# DroneCode_probe-v22.net
KiCad netlist of a schematic drawn in EAGLE
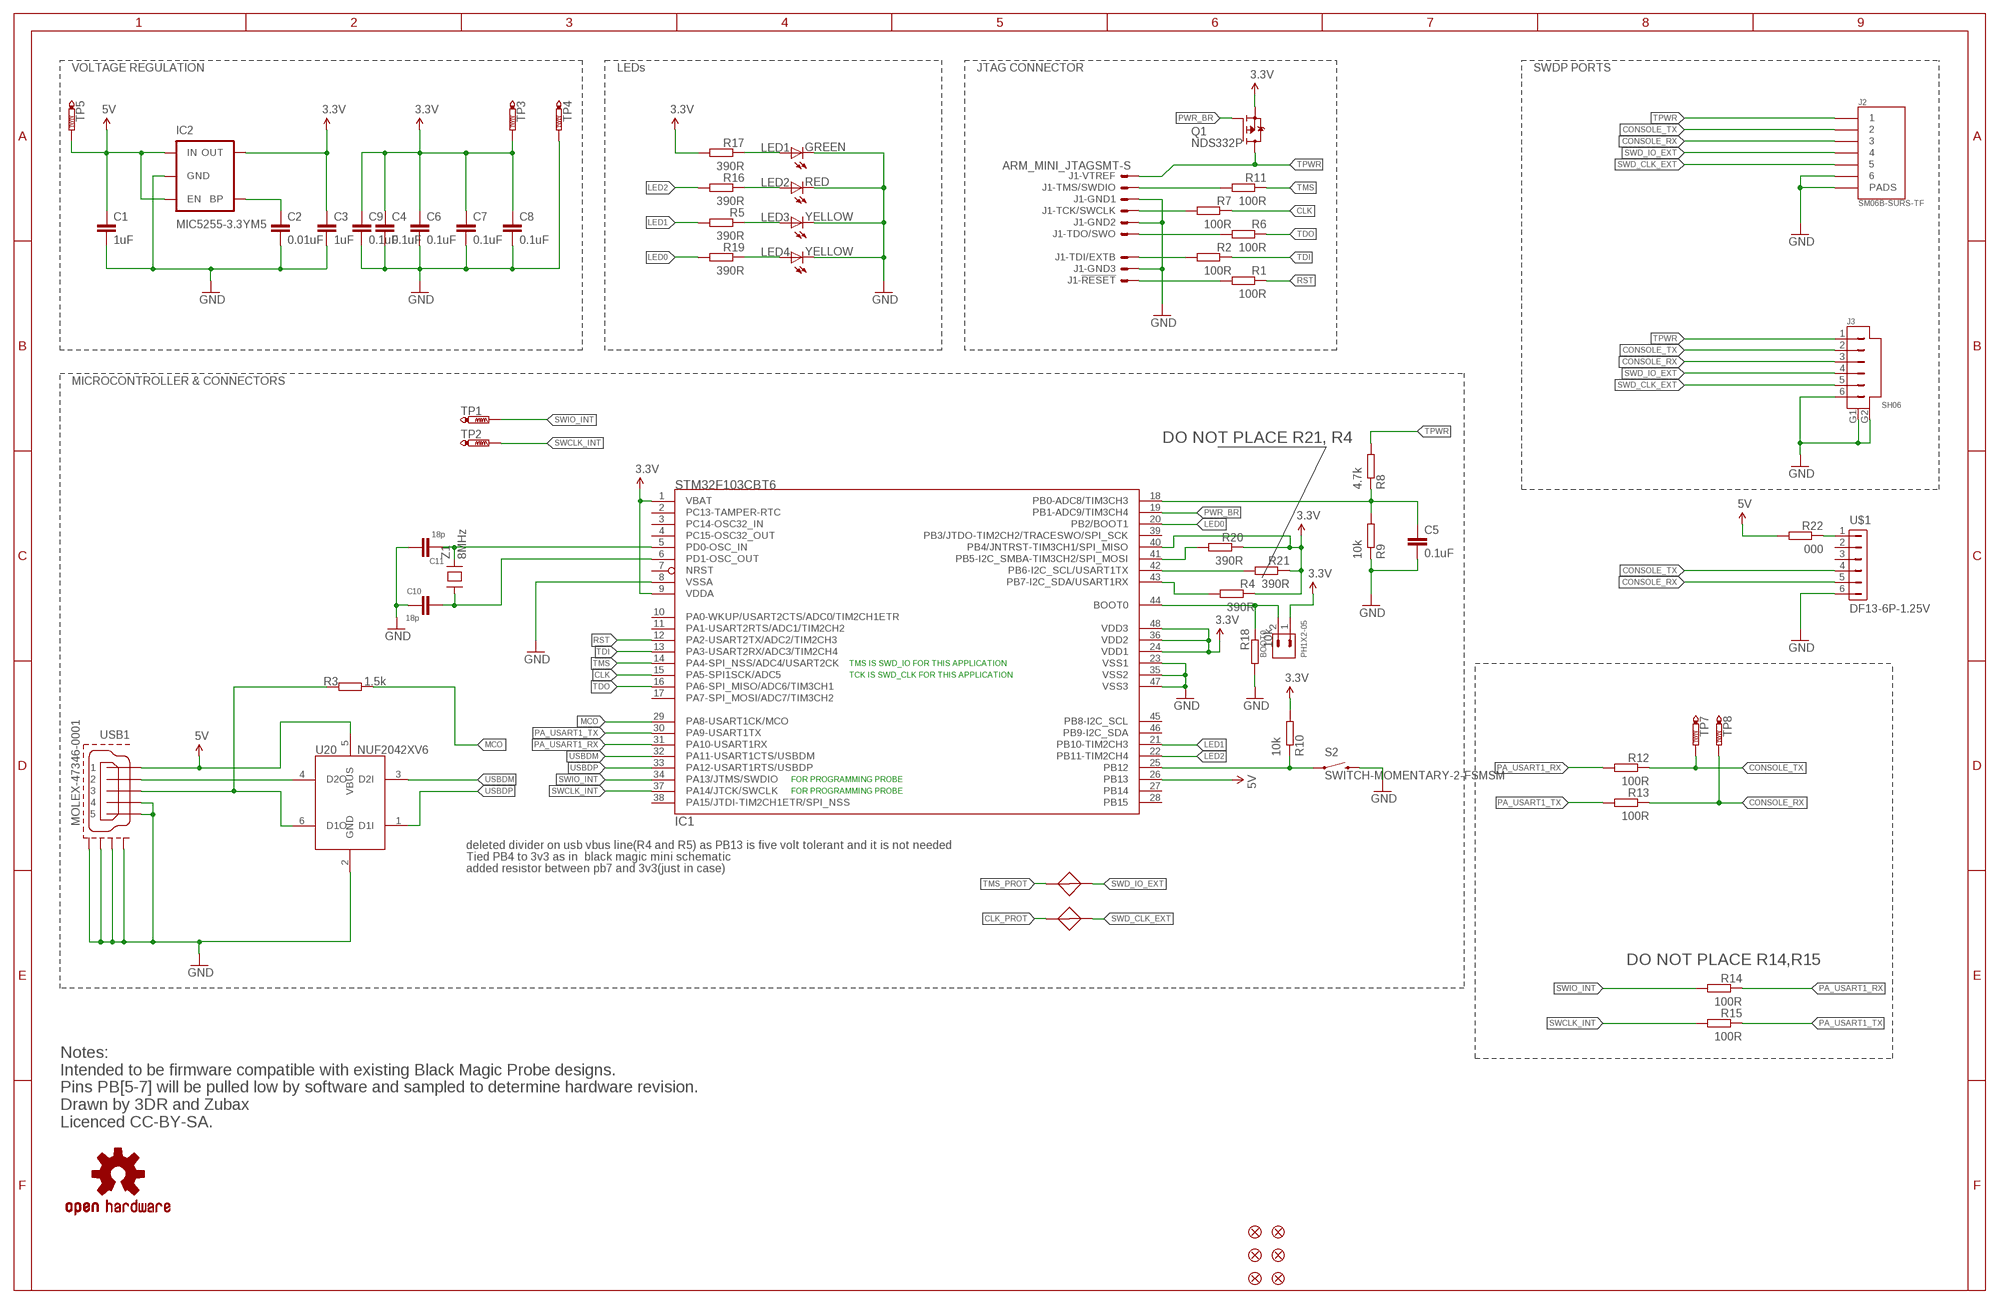
[diagram p0: schematic, sheet 1]

(export (version "E")
  (design (tool "Eeschema 10.0.6"))
  (components
    (comp (ref "BOOT0")
      (value "PH1X2-05")
      (footprint "eagle-import:PH005-1-2")
      (libsource (lib "eagle-import") (part "PH1X2-05"))
    )
    (comp (ref "C1")
      (value "1uF")
      (footprint "eagle-import:0603-CAP")
      (fields (field (name "PARTNO") "CC0603ZRY5V7BB105"))
      (libsource (lib "eagle-import") (part "CAPACITOR-0603"))
    )
    (comp (ref "C2")
      (value "0.01uF")
      (footprint "eagle-import:0402-CAP")
      (fields (field (name "PARTNO") "EMK105B7103KV-F"))
      (libsource (lib "eagle-import") (part "CAPACITOR-0402"))
    )
    (comp (ref "C3")
      (value "1uF")
      (footprint "eagle-import:0603-CAP")
      (fields (field (name "PARTNO") "CC0603ZRY5V7BB105"))
      (libsource (lib "eagle-import") (part "CAPACITOR-0603"))
    )
    (comp (ref "C4")
      (value "0.1uF")
      (footprint "eagle-import:0402-CAP")
      (fields (field (name "PARTNO") "C1005X7R1E104K050BB"))
      (libsource (lib "eagle-import") (part "CAPACITOR-0402"))
    )
    (comp (ref "C5")
      (value "0.1uF")
      (footprint "eagle-import:0402-CAP")
      (fields (field (name "PARTNO") "C1005X7R1E104K050BB"))
      (libsource (lib "eagle-import") (part "CAPACITOR-0402"))
    )
    (comp (ref "C6")
      (value "0.1uF")
      (footprint "eagle-import:0402-CAP")
      (fields (field (name "PARTNO") "C1005X7R1E104K050BB"))
      (libsource (lib "eagle-import") (part "CAPACITOR-0402"))
    )
    (comp (ref "C7")
      (value "0.1uF")
      (footprint "eagle-import:0402-CAP")
      (fields (field (name "PARTNO") "C1005X7R1E104K050BB"))
      (libsource (lib "eagle-import") (part "CAPACITOR-0402"))
    )
    (comp (ref "C8")
      (value "0.1uF")
      (footprint "eagle-import:0402-CAP")
      (fields (field (name "PARTNO") "C1005X7R1E104K050BB"))
      (libsource (lib "eagle-import") (part "CAPACITOR-0402"))
    )
    (comp (ref "C9")
      (value "0.1uF")
      (footprint "eagle-import:0402-CAP")
      (fields (field (name "PARTNO") "C1005X7R1E104K050BB"))
      (libsource (lib "eagle-import") (part "CAPACITOR-0402"))
    )
    (comp (ref "C10")
      (value "18p")
      (footprint "eagle-import:0402")
      (fields (field (name "DIGIKEY#") "CL05C180JB5NNNC") (field (name "MANF#") "CL05C180JB5NNNC"))
      (libsource (lib "eagle-import") (part "C0402"))
    )
    (comp (ref "C11")
      (value "18p")
      (footprint "eagle-import:0402")
      (fields (field (name "DIGIKEY#") "CL05C180JB5NNNC") (field (name "MANF#") "CL05C180JB5NNNC"))
      (libsource (lib "eagle-import") (part "C0402"))
    )
    (comp (ref "IC1")
      (value "STM32F103CBT6")
      (footprint "eagle-import:LQFP48")
      (libsource (lib "eagle-import") (part "STM32F102CBT6"))
    )
    (comp (ref "IC2")
      (value "MIC5255-3.3YM5")
      (footprint "eagle-import:SOT23-5")
      (fields (field (name "PARTNO") "MIC5255-3.3YM5 TR"))
      (libsource (lib "eagle-import") (part "V_REG_LDOSMD"))
    )
    (comp (ref "J1")
      (value "ARM_MINI_JTAGSMT-S")
      (footprint "eagle-import:200215-00010T1LF")
      (fields (field (name "PARTNO") "20021521-00010T1LF") (field (name "DIGIKEY#") "609-4054-ND"))
      (libsource (lib "eagle-import") (part "ARM_MINI_JTAGSMT-S"))
    )
    (comp (ref "J2")
      (value "SM06B-SURS-TF")
      (footprint "eagle-import:SM02B-SURS-TF")
      (fields (field (name "PARTNO") "SM06B-SURS-TF(LF)(SN)"))
      (libsource (lib "eagle-import") (part "SM06B-SURS-TF"))
    )
    (comp (ref "J3")
      (value "SH06")
      (footprint "eagle-import:SH06B")
      (fields (field (name "PARTNO") "SM06B-SRSS-TB"))
      (libsource (lib "eagle-import") (part "SH06"))
    )
    (comp (ref "J4")
      (value "JUNCTION")
      (footprint "eagle-import:JUNCTION")
      (libsource (lib "eagle-import") (part "JUNCTION"))
    )
    (comp (ref "J5")
      (value "JUNCTION")
      (footprint "eagle-import:JUNCTION")
      (libsource (lib "eagle-import") (part "JUNCTION"))
    )
    (comp (ref "JP1")
      (value "FIDUCIAL1X2")
      (footprint "eagle-import:FIDUCIAL-1X2")
      (libsource (lib "eagle-import") (part "FIDUCIAL1X2"))
    )
    (comp (ref "JP2")
      (value "FIDUCIAL1X2")
      (footprint "eagle-import:FIDUCIAL-1X2")
      (libsource (lib "eagle-import") (part "FIDUCIAL1X2"))
    )
    (comp (ref "JP3")
      (value "FIDUCIAL1X2")
      (footprint "eagle-import:FIDUCIAL-1X2")
      (libsource (lib "eagle-import") (part "FIDUCIAL1X2"))
    )
    (comp (ref "JP4")
      (value "FIDUCIAL1X2")
      (footprint "eagle-import:FIDUCIAL-1X2")
      (libsource (lib "eagle-import") (part "FIDUCIAL1X2"))
    )
    (comp (ref "JP5")
      (value "FIDUCIAL1X2")
      (footprint "eagle-import:FIDUCIAL-1X2")
      (libsource (lib "eagle-import") (part "FIDUCIAL1X2"))
    )
    (comp (ref "JP6")
      (value "FIDUCIAL1X2")
      (footprint "eagle-import:FIDUCIAL-1X2")
      (libsource (lib "eagle-import") (part "FIDUCIAL1X2"))
    )
    (comp (ref "LED1")
      (value "GREEN")
      (footprint "eagle-import:0603-LED")
      (fields (field (name "PARTNO") "APT1608SGC"))
      (libsource (lib "eagle-import") (part "LED-0603"))
    )
    (comp (ref "LED2")
      (value "RED")
      (footprint "eagle-import:0603-LED")
      (fields (field (name "PARTNO") "APT1608SRCPRV"))
      (libsource (lib "eagle-import") (part "LED-0603"))
    )
    (comp (ref "LED3")
      (value "YELLOW")
      (footprint "eagle-import:0603-LED")
      (fields (field (name "PARTNO") "APT1608YC"))
      (libsource (lib "eagle-import") (part "LED-0603"))
    )
    (comp (ref "LED4")
      (value "YELLOW")
      (footprint "eagle-import:0603-LED")
      (fields (field (name "PARTNO") "APT1608YC"))
      (libsource (lib "eagle-import") (part "LED-0603"))
    )
    (comp (ref "Q1")
      (value "NDS332P")
      (footprint "eagle-import:SOT23B-3")
      (fields (field (name "MANF") "Fairchild Semiconductor"))
      (libsource (lib "eagle-import") (part "NDS332P"))
    )
    (comp (ref "R1")
      (value "100R")
      (footprint "eagle-import:0402-RES")
      (fields (field (name "PARTNO") "RC0402FR-07100RL"))
      (libsource (lib "eagle-import") (part "RESISTOR-0402"))
    )
    (comp (ref "R2")
      (value "100R")
      (footprint "eagle-import:0402-RES")
      (fields (field (name "PARTNO") "RC0402FR-07100RL"))
      (libsource (lib "eagle-import") (part "RESISTOR-0402"))
    )
    (comp (ref "R3")
      (value "1.5k")
      (footprint "eagle-import:0402-RES")
      (fields (field (name "PARTNO") "RC0402FR-071K5L"))
      (libsource (lib "eagle-import") (part "RESISTOR-0402"))
    )
    (comp (ref "R4")
      (value "390R")
      (footprint "eagle-import:0402-RES")
      (fields (field (name "PARTNO") "CRCW0402390RJNED"))
      (libsource (lib "eagle-import") (part "RESISTOR-0402"))
    )
    (comp (ref "R5")
      (value "390R")
      (footprint "eagle-import:0402-RES")
      (fields (field (name "PARTNO") "CRCW0402390RJNED"))
      (libsource (lib "eagle-import") (part "RESISTOR-0402"))
    )
    (comp (ref "R6")
      (value "100R")
      (footprint "eagle-import:0402-RES")
      (fields (field (name "PARTNO") "RC0402FR-07100RL"))
      (libsource (lib "eagle-import") (part "RESISTOR-0402"))
    )
    (comp (ref "R7")
      (value "100R")
      (footprint "eagle-import:0402-RES")
      (fields (field (name "PARTNO") "RC0402FR-07100RL"))
      (libsource (lib "eagle-import") (part "RESISTOR-0402"))
    )
    (comp (ref "R8")
      (value "4.7k")
      (footprint "eagle-import:0402-RES")
      (fields (field (name "PARTNO") "ERJ-2RKF4701X"))
      (libsource (lib "eagle-import") (part "RESISTOR-0402"))
    )
    (comp (ref "R9")
      (value "10k")
      (footprint "eagle-import:0402-RES")
      (fields (field (name "PARTNO") "RC0402FR-0710KL"))
      (libsource (lib "eagle-import") (part "RESISTOR-0402"))
    )
    (comp (ref "R10")
      (value "10k")
      (footprint "eagle-import:0402-RES")
      (fields (field (name "PARTNO") "RC0402FR-0710KL"))
      (libsource (lib "eagle-import") (part "RESISTOR-0402"))
    )
    (comp (ref "R11")
      (value "100R")
      (footprint "eagle-import:0402-RES")
      (fields (field (name "PARTNO") "RC0402FR-07100RL"))
      (libsource (lib "eagle-import") (part "RESISTOR-0402"))
    )
    (comp (ref "R12")
      (value "100R")
      (footprint "eagle-import:0402-RES")
      (fields (field (name "PARTNO") "RC0402FR-07100RL"))
      (libsource (lib "eagle-import") (part "RESISTOR-0402"))
    )
    (comp (ref "R13")
      (value "100R")
      (footprint "eagle-import:0402-RES")
      (fields (field (name "PARTNO") "RC0402FR-07100RL"))
      (libsource (lib "eagle-import") (part "RESISTOR-0402"))
    )
    (comp (ref "R14")
      (value "100R")
      (footprint "eagle-import:0402-RES")
      (fields (field (name "PARTNO") "RC0402FR-07100RL"))
      (libsource (lib "eagle-import") (part "RESISTOR-0402"))
    )
    (comp (ref "R15")
      (value "100R")
      (footprint "eagle-import:0402-RES")
      (fields (field (name "PARTNO") "RC0402FR-07100RL"))
      (libsource (lib "eagle-import") (part "RESISTOR-0402"))
    )
    (comp (ref "R16")
      (value "390R")
      (footprint "eagle-import:0402-RES")
      (fields (field (name "PARTNO") "CRCW0402390RJNED"))
      (libsource (lib "eagle-import") (part "RESISTOR-0402"))
    )
    (comp (ref "R17")
      (value "390R")
      (footprint "eagle-import:0402-RES")
      (fields (field (name "PARTNO") "CRCW0402390RJNED"))
      (libsource (lib "eagle-import") (part "RESISTOR-0402"))
    )
    (comp (ref "R18")
      (value "10k")
      (footprint "eagle-import:0402-RES")
      (fields (field (name "PARTNO") "RC0402FR-0710KL"))
      (libsource (lib "eagle-import") (part "RESISTOR-0402"))
    )
    (comp (ref "R19")
      (value "390R")
      (footprint "eagle-import:0402-RES")
      (fields (field (name "PARTNO") "CRCW0402390RJNED"))
      (libsource (lib "eagle-import") (part "RESISTOR-0402"))
    )
    (comp (ref "R20")
      (value "390R")
      (footprint "eagle-import:0402-RES")
      (fields (field (name "PARTNO") "CRCW0402390RJNED"))
      (libsource (lib "eagle-import") (part "RESISTOR-0402"))
    )
    (comp (ref "R21")
      (value "390R")
      (footprint "eagle-import:0402-RES")
      (fields (field (name "PARTNO") "CRCW0402390RJNED"))
      (libsource (lib "eagle-import") (part "RESISTOR-0402"))
    )
    (comp (ref "R22")
      (value "000")
      (footprint "eagle-import:0402-RES")
      (fields (field (name "PARTNO") "ERJ-2GE0R00X"))
      (libsource (lib "eagle-import") (part "RESISTOR-0402"))
    )
    (comp (ref "S2")
      (value "SWITCH-MOMENTARY-2-FSMSM")
      (footprint "eagle-import:FSMSM")
      (fields (field (name "MANF") "TE Connectivity Alcoswitch Switches"))
      (libsource (lib "eagle-import") (part "SWITCH-MOMENTARY-2-FSMSM"))
    )
    (comp (ref "TP1")
      (value "PTR1B1,27")
      (footprint "eagle-import:B1,27")
      (libsource (lib "eagle-import") (part "PTR1B1,27"))
    )
    (comp (ref "TP2")
      (value "PTR1B1,27")
      (footprint "eagle-import:B1,27")
      (libsource (lib "eagle-import") (part "PTR1B1,27"))
    )
    (comp (ref "TP3")
      (value "PTR1B1,27")
      (footprint "eagle-import:B1,27")
      (libsource (lib "eagle-import") (part "PTR1B1,27"))
    )
    (comp (ref "TP4")
      (value "PTR1B1,27")
      (footprint "eagle-import:B1,27")
      (libsource (lib "eagle-import") (part "PTR1B1,27"))
    )
    (comp (ref "TP5")
      (value "PTR1B1,27")
      (footprint "eagle-import:B1,27")
      (libsource (lib "eagle-import") (part "PTR1B1,27"))
    )
    (comp (ref "TP7")
      (value "PTR1B1,27")
      (footprint "eagle-import:B1,27")
      (libsource (lib "eagle-import") (part "PTR1B1,27"))
    )
    (comp (ref "TP8")
      (value "PTR1B1,27")
      (footprint "eagle-import:B1,27")
      (libsource (lib "eagle-import") (part "PTR1B1,27"))
    )
    (comp (ref "U$1")
      (value "DF13-6P-1.25V")
      (footprint "eagle-import:DF13C-6P-1.25V")
      (fields (field (name "PARTNO") "DF13C-6P-1.25V(20)"))
      (libsource (lib "eagle-import") (part "DF13-6P-1.25V"))
    )
    (comp (ref "U$5")
      (value "OSHW-LOGOL")
      (footprint "eagle-import:OSHW-LOGO-L")
      (libsource (lib "eagle-import") (part "OSHW-LOGOL"))
    )
    (comp (ref "U20")
      (value "NUF2042XV6")
      (footprint "eagle-import:SOT563-6")
      (fields (field (name "PARTNO") "NUF2042XV6T1G"))
      (libsource (lib "eagle-import") (part "NUF2042XV6"))
    )
    (comp (ref "USB1")
      (value "MOLEX-47346-0001")
      (footprint "eagle-import:MOLEX-47346-0001")
      (fields (field (name "PARTNO") "47346-0001"))
      (libsource (lib "eagle-import") (part "MOLEX-47346-0001"))
    )
    (comp (ref "Z1")
      (value "8MHz")
      (footprint "eagle-import:NX3225GD")
      (libsource (lib "eagle-import") (part "CRYSTAL-NX3225GD"))
    )
  )
  (nets
    (net (code "1") (name "3.3V") (class "Default")
      (node (ref "BOOT0") (pin "1") (pinfunction "1_1") (pintype "bidirectional"))
      (node (ref "C3") (pin "P$1") (pinfunction "1_P$1") (pintype "passive"))
      (node (ref "C4") (pin "P$1") (pinfunction "1_P$1") (pintype "passive"))
      (node (ref "C6") (pin "P$1") (pinfunction "1_P$1") (pintype "passive"))
      (node (ref "C7") (pin "P$1") (pinfunction "1_P$1") (pintype "passive"))
      (node (ref "C8") (pin "P$1") (pinfunction "1_P$1") (pintype "passive"))
      (node (ref "C9") (pin "P$1") (pinfunction "1_P$1") (pintype "passive"))
      (node (ref "IC1") (pin "1") (pinfunction "VBAT_1") (pintype "power_in"))
      (node (ref "IC1") (pin "24") (pinfunction "VDD1_24") (pintype "power_in"))
      (node (ref "IC1") (pin "36") (pinfunction "VDD2_36") (pintype "power_in"))
      (node (ref "IC1") (pin "40") (pinfunction "PB4/JNTRST-TIM3CH1/SPI_MISO_40") (pintype "bidirectional"))
      (node (ref "IC1") (pin "48") (pinfunction "VDD3_48") (pintype "power_in"))
      (node (ref "IC1") (pin "9") (pinfunction "VDDA_9") (pintype "power_in"))
      (node (ref "IC2") (pin "5") (pinfunction "OUT_5") (pintype "passive"))
      (node (ref "Q1") (pin "S") (pinfunction "S_S") (pintype "passive"))
      (node (ref "R10") (pin "P$2") (pinfunction "2_P$2") (pintype "passive"))
      (node (ref "R17") (pin "P$2") (pinfunction "2_P$2") (pintype "passive"))
      (node (ref "R20") (pin "P$1") (pinfunction "1_P$1") (pintype "passive"))
      (node (ref "R21") (pin "P$1") (pinfunction "1_P$1") (pintype "passive"))
      (node (ref "R4") (pin "P$1") (pinfunction "1_P$1") (pintype "passive"))
      (node (ref "TP3") (pin "TP") (pinfunction "TP_TP") (pintype "input"))
    )
    (net (code "2") (name "5V") (class "Default")
      (node (ref "C1") (pin "P$1") (pinfunction "1_P$1") (pintype "passive"))
      (node (ref "IC1") (pin "26") (pinfunction "PB13_26") (pintype "bidirectional"))
      (node (ref "IC2") (pin "1") (pinfunction "IN_1") (pintype "input"))
      (node (ref "IC2") (pin "3") (pinfunction "EN_3") (pintype "input"))
      (node (ref "R22") (pin "P$2") (pinfunction "2_P$2") (pintype "passive"))
      (node (ref "TP5") (pin "TP") (pinfunction "TP_TP") (pintype "input"))
      (node (ref "U20") (pin "5") (pinfunction "VBUS_5") (pintype "bidirectional"))
      (node (ref "USB1") (pin "VBUS") (pinfunction "1_VBUS") (pintype "power_in"))
    )
    (net (code "3") (name "CLK") (class "Default")
      (node (ref "IC1") (pin "15") (pinfunction "PA5-SPI1SCK/ADC5_15") (pintype "bidirectional"))
      (node (ref "R7") (pin "P$1") (pinfunction "1_P$1") (pintype "passive"))
    )
    (net (code "4") (name "CLK_PROT") (class "Default")
      (node (ref "J1") (pin "4") (pinfunction "S_4") (pintype "passive"))
      (node (ref "J5") (pin "P$1") (pinfunction "1_P$1") (pintype "bidirectional"))
      (node (ref "R7") (pin "P$2") (pinfunction "2_P$2") (pintype "passive"))
    )
    (net (code "5") (name "CONSOLE_RX") (class "Default")
      (node (ref "J2") (pin "3") (pinfunction "3_3") (pintype "bidirectional"))
      (node (ref "J3") (pin "3") (pinfunction "3_3") (pintype "passive"))
      (node (ref "R13") (pin "P$1") (pinfunction "1_P$1") (pintype "passive"))
      (node (ref "TP8") (pin "TP") (pinfunction "TP_TP") (pintype "input"))
      (node (ref "U$1") (pin "5") (pinfunction "5_5") (pintype "passive"))
    )
    (net (code "6") (name "CONSOLE_TX") (class "Default")
      (node (ref "J2") (pin "2") (pinfunction "2_2") (pintype "bidirectional"))
      (node (ref "J3") (pin "2") (pinfunction "2_2") (pintype "passive"))
      (node (ref "R12") (pin "P$1") (pinfunction "1_P$1") (pintype "passive"))
      (node (ref "TP7") (pin "TP") (pinfunction "TP_TP") (pintype "input"))
      (node (ref "U$1") (pin "4") (pinfunction "4_4") (pintype "passive"))
    )
    (net (code "7") (name "GND") (class "Default")
      (node (ref "C1") (pin "P$2") (pinfunction "2_P$2") (pintype "passive"))
      (node (ref "C10") (pin "2") (pinfunction "2_2") (pintype "passive"))
      (node (ref "C11") (pin "1") (pinfunction "1_1") (pintype "passive"))
      (node (ref "C2") (pin "P$2") (pinfunction "2_P$2") (pintype "passive"))
      (node (ref "C3") (pin "P$2") (pinfunction "2_P$2") (pintype "passive"))
      (node (ref "C4") (pin "P$2") (pinfunction "2_P$2") (pintype "passive"))
      (node (ref "C5") (pin "P$2") (pinfunction "2_P$2") (pintype "passive"))
      (node (ref "C6") (pin "P$2") (pinfunction "2_P$2") (pintype "passive"))
      (node (ref "C7") (pin "P$2") (pinfunction "2_P$2") (pintype "passive"))
      (node (ref "C8") (pin "P$2") (pinfunction "2_P$2") (pintype "passive"))
      (node (ref "C9") (pin "P$2") (pinfunction "2_P$2") (pintype "passive"))
      (node (ref "IC1") (pin "23") (pinfunction "VSS1_23") (pintype "power_in"))
      (node (ref "IC1") (pin "35") (pinfunction "VSS2_35") (pintype "power_in"))
      (node (ref "IC1") (pin "47") (pinfunction "VSS3_47") (pintype "power_in"))
      (node (ref "IC1") (pin "8") (pinfunction "VSSA_8") (pintype "power_in"))
      (node (ref "IC2") (pin "2") (pinfunction "GND_2") (pintype "input"))
      (node (ref "J1") (pin "3") (pinfunction "S_3") (pintype "passive"))
      (node (ref "J1") (pin "5") (pinfunction "S_5") (pintype "passive"))
      (node (ref "J1") (pin "9") (pinfunction "S_9") (pintype "passive"))
      (node (ref "J2") (pin "6") (pinfunction "6_6") (pintype "bidirectional"))
      (node (ref "J2") (pin "PAD-L") (pinfunction "PADS_PAD-L") (pintype "bidirectional"))
      (node (ref "J2") (pin "PAD-R") (pinfunction "PADS_PAD-R") (pintype "bidirectional"))
      (node (ref "J3") (pin "6") (pinfunction "6_6") (pintype "passive"))
      (node (ref "J3") (pin "G1") (pinfunction "G1_G1") (pintype "passive"))
      (node (ref "J3") (pin "G2") (pinfunction "G2_G2") (pintype "passive"))
      (node (ref "LED1") (pin "C") (pinfunction "C_C") (pintype "passive"))
      (node (ref "LED2") (pin "C") (pinfunction "C_C") (pintype "passive"))
      (node (ref "LED3") (pin "C") (pinfunction "C_C") (pintype "passive"))
      (node (ref "LED4") (pin "C") (pinfunction "C_C") (pintype "passive"))
      (node (ref "R18") (pin "P$2") (pinfunction "2_P$2") (pintype "passive"))
      (node (ref "R9") (pin "P$1") (pinfunction "1_P$1") (pintype "passive"))
      (node (ref "S2") (pin "P$2") (pinfunction "2_P$2") (pintype "passive"))
      (node (ref "TP4") (pin "TP") (pinfunction "TP_TP") (pintype "input"))
      (node (ref "U$1") (pin "6") (pinfunction "6_6") (pintype "passive"))
      (node (ref "U20") (pin "2") (pinfunction "GND_2") (pintype "bidirectional"))
      (node (ref "USB1") (pin "GND") (pinfunction "5_GND") (pintype "power_in"))
      (node (ref "USB1") (pin "GND1") (pinfunction "GND1_GND1") (pintype "bidirectional"))
      (node (ref "USB1") (pin "GND2") (pinfunction "GND2_GND2") (pintype "bidirectional"))
      (node (ref "USB1") (pin "GND3") (pinfunction "GND3_GND3") (pintype "bidirectional"))
      (node (ref "USB1") (pin "GND4") (pinfunction "GND4_GND4") (pintype "bidirectional"))
      (node (ref "USB1") (pin "ID") (pinfunction "4_ID") (pintype "passive"))
    )
    (net (code "8") (name "LED0") (class "Default")
      (node (ref "IC1") (pin "20") (pinfunction "PB2/BOOT1_20") (pintype "bidirectional"))
      (node (ref "R19") (pin "P$2") (pinfunction "2_P$2") (pintype "passive"))
    )
    (net (code "9") (name "LED1") (class "Default")
      (node (ref "IC1") (pin "21") (pinfunction "PB10-TIM2CH3_21") (pintype "bidirectional"))
      (node (ref "R5") (pin "P$2") (pinfunction "2_P$2") (pintype "passive"))
    )
    (net (code "10") (name "LED2") (class "Default")
      (node (ref "IC1") (pin "22") (pinfunction "PB11-TIM2CH4_22") (pintype "bidirectional"))
      (node (ref "R16") (pin "P$2") (pinfunction "2_P$2") (pintype "passive"))
    )
    (net (code "11") (name "MCO") (class "Default")
      (node (ref "IC1") (pin "29") (pinfunction "PA8-USART1CK/MCO_29") (pintype "bidirectional"))
      (node (ref "R3") (pin "P$2") (pinfunction "2_P$2") (pintype "passive"))
    )
    (net (code "12") (name "Net-(C2-1)") (class "Default")
      (node (ref "C2") (pin "P$1") (pinfunction "1_P$1") (pintype "passive"))
      (node (ref "IC2") (pin "4") (pinfunction "BP_4") (pintype "input"))
    )
    (net (code "13") (name "Net-(C5-1)") (class "Default")
      (node (ref "C5") (pin "P$1") (pinfunction "1_P$1") (pintype "passive"))
      (node (ref "IC1") (pin "18") (pinfunction "PB0-ADC8/TIM3CH3_18") (pintype "bidirectional"))
      (node (ref "R8") (pin "P$1") (pinfunction "1_P$1") (pintype "passive"))
      (node (ref "R9") (pin "P$2") (pinfunction "2_P$2") (pintype "passive"))
    )
    (net (code "14") (name "Net-(IC1-BOOT0)") (class "Default")
      (node (ref "BOOT0") (pin "2") (pinfunction "2_2") (pintype "bidirectional"))
      (node (ref "IC1") (pin "44") (pinfunction "BOOT0_44") (pintype "input"))
      (node (ref "R18") (pin "P$1") (pinfunction "1_P$1") (pintype "passive"))
    )
    (net (code "15") (name "Net-(IC1-PB5-I2C_SMBA-TIM3CH2{slash}SPI_MOSI)") (class "Default")
      (node (ref "IC1") (pin "41") (pinfunction "PB5-I2C_SMBA-TIM3CH2/SPI_MOSI_41") (pintype "bidirectional"))
      (node (ref "R20") (pin "P$2") (pinfunction "2_P$2") (pintype "passive"))
    )
    (net (code "16") (name "Net-(IC1-PB6-I2C_SCL{slash}USART1TX)") (class "Default")
      (node (ref "IC1") (pin "42") (pinfunction "PB6-I2C_SCL/USART1TX_42") (pintype "bidirectional"))
      (node (ref "R21") (pin "P$2") (pinfunction "2_P$2") (pintype "passive"))
    )
    (net (code "17") (name "Net-(IC1-PB7-I2C_SDA{slash}USART1RX)") (class "Default")
      (node (ref "IC1") (pin "43") (pinfunction "PB7-I2C_SDA/USART1RX_43") (pintype "bidirectional"))
      (node (ref "R4") (pin "P$2") (pinfunction "2_P$2") (pintype "passive"))
    )
    (net (code "18") (name "Net-(IC1-PB12)") (class "Default")
      (node (ref "IC1") (pin "25") (pinfunction "PB12_25") (pintype "bidirectional"))
      (node (ref "R10") (pin "P$1") (pinfunction "1_P$1") (pintype "passive"))
      (node (ref "S2") (pin "P$1") (pinfunction "1_P$1") (pintype "passive"))
    )
    (net (code "19") (name "Net-(IC1-PD0-OSC_IN)") (class "Default")
      (node (ref "C11") (pin "2") (pinfunction "2_2") (pintype "passive"))
      (node (ref "IC1") (pin "5") (pinfunction "PD0-OSC_IN_5") (pintype "input"))
      (node (ref "Z1") (pin "2") (pinfunction "2_2") (pintype "passive"))
    )
    (net (code "20") (name "Net-(IC1-PD1-OSC_OUT)") (class "Default")
      (node (ref "C10") (pin "1") (pinfunction "1_1") (pintype "passive"))
      (node (ref "IC1") (pin "6") (pinfunction "PD1-OSC_OUT_6") (pintype "output"))
      (node (ref "Z1") (pin "1") (pinfunction "1_1") (pintype "passive"))
    )
    (net (code "21") (name "Net-(J1A-S)") (class "Default")
      (node (ref "J1") (pin "10") (pinfunction "S_10") (pintype "passive"))
      (node (ref "R1") (pin "P$2") (pinfunction "2_P$2") (pintype "passive"))
    )
    (net (code "22") (name "Net-(J1F-S)") (class "Default")
      (node (ref "J1") (pin "8") (pinfunction "S_8") (pintype "passive"))
      (node (ref "R2") (pin "P$2") (pinfunction "2_P$2") (pintype "passive"))
    )
    (net (code "23") (name "Net-(J1G-S)") (class "Default")
      (node (ref "J1") (pin "6") (pinfunction "S_6") (pintype "passive"))
      (node (ref "R6") (pin "P$2") (pinfunction "2_P$2") (pintype "passive"))
    )
    (net (code "24") (name "Net-(R3-1)") (class "Default")
      (node (ref "R3") (pin "P$1") (pinfunction "1_P$1") (pintype "passive"))
      (node (ref "U20") (pin "6") (pinfunction "D1O_6") (pintype "bidirectional"))
      (node (ref "USB1") (pin "D+") (pinfunction "3_D+") (pintype "bidirectional"))
    )
    (net (code "25") (name "Net-(R5-1)") (class "Default")
      (node (ref "LED3") (pin "A") (pinfunction "A_A") (pintype "passive"))
      (node (ref "R5") (pin "P$1") (pinfunction "1_P$1") (pintype "passive"))
    )
    (net (code "26") (name "Net-(R16-1)") (class "Default")
      (node (ref "LED2") (pin "A") (pinfunction "A_A") (pintype "passive"))
      (node (ref "R16") (pin "P$1") (pinfunction "1_P$1") (pintype "passive"))
    )
    (net (code "27") (name "Net-(R17-1)") (class "Default")
      (node (ref "LED1") (pin "A") (pinfunction "A_A") (pintype "passive"))
      (node (ref "R17") (pin "P$1") (pinfunction "1_P$1") (pintype "passive"))
    )
    (net (code "28") (name "Net-(R19-1)") (class "Default")
      (node (ref "LED4") (pin "A") (pinfunction "A_A") (pintype "passive"))
      (node (ref "R19") (pin "P$1") (pinfunction "1_P$1") (pintype "passive"))
    )
    (net (code "29") (name "Net-(R22-1)") (class "Default")
      (node (ref "R22") (pin "P$1") (pinfunction "1_P$1") (pintype "passive"))
      (node (ref "U$1") (pin "1") (pinfunction "1_1") (pintype "passive"))
    )
    (net (code "30") (name "Net-(U20-D2O)") (class "Default")
      (node (ref "U20") (pin "4") (pinfunction "D2O_4") (pintype "bidirectional"))
      (node (ref "USB1") (pin "D-") (pinfunction "2_D-") (pintype "bidirectional"))
    )
    (net (code "31") (name "PA_USART1_RX") (class "Default")
      (node (ref "IC1") (pin "31") (pinfunction "PA10-USART1RX_31") (pintype "bidirectional"))
      (node (ref "R12") (pin "P$2") (pinfunction "2_P$2") (pintype "passive"))
      (node (ref "R14") (pin "P$1") (pinfunction "1_P$1") (pintype "passive"))
    )
    (net (code "32") (name "PA_USART1_TX") (class "Default")
      (node (ref "IC1") (pin "30") (pinfunction "PA9-USART1TX_30") (pintype "bidirectional"))
      (node (ref "R13") (pin "P$2") (pinfunction "2_P$2") (pintype "passive"))
      (node (ref "R15") (pin "P$1") (pinfunction "1_P$1") (pintype "passive"))
    )
    (net (code "33") (name "PWR_BR") (class "Default")
      (node (ref "IC1") (pin "19") (pinfunction "PB1-ADC9/TIM3CH4_19") (pintype "bidirectional"))
      (node (ref "Q1") (pin "G") (pinfunction "G_G") (pintype "passive"))
    )
    (net (code "34") (name "RST") (class "Default")
      (node (ref "IC1") (pin "12") (pinfunction "PA2-USART2TX/ADC2/TIM2CH3_12") (pintype "bidirectional"))
      (node (ref "R1") (pin "P$1") (pinfunction "1_P$1") (pintype "passive"))
    )
    (net (code "35") (name "SWCLK_INT") (class "Default")
      (node (ref "IC1") (pin "37") (pinfunction "PA14/JTCK/SWCLK_37") (pintype "bidirectional"))
      (node (ref "R15") (pin "P$2") (pinfunction "2_P$2") (pintype "passive"))
      (node (ref "TP2") (pin "TP") (pinfunction "TP_TP") (pintype "input"))
    )
    (net (code "36") (name "SWD_CLK_EXT") (class "Default")
      (node (ref "J2") (pin "5") (pinfunction "5_5") (pintype "bidirectional"))
      (node (ref "J3") (pin "5") (pinfunction "5_5") (pintype "passive"))
      (node (ref "J5") (pin "P$2") (pinfunction "2_P$2") (pintype "bidirectional"))
    )
    (net (code "37") (name "SWD_IO_EXT") (class "Default")
      (node (ref "J2") (pin "4") (pinfunction "4_4") (pintype "bidirectional"))
      (node (ref "J3") (pin "4") (pinfunction "4_4") (pintype "passive"))
      (node (ref "J4") (pin "P$2") (pinfunction "2_P$2") (pintype "bidirectional"))
    )
    (net (code "38") (name "SWIO_INT") (class "Default")
      (node (ref "IC1") (pin "34") (pinfunction "PA13/JTMS/SWDIO_34") (pintype "bidirectional"))
      (node (ref "R14") (pin "P$2") (pinfunction "2_P$2") (pintype "passive"))
      (node (ref "TP1") (pin "TP") (pinfunction "TP_TP") (pintype "input"))
    )
    (net (code "39") (name "TDI") (class "Default")
      (node (ref "IC1") (pin "13") (pinfunction "PA3-USART2RX/ADC3/TIM2CH4_13") (pintype "bidirectional"))
      (node (ref "R2") (pin "P$1") (pinfunction "1_P$1") (pintype "passive"))
    )
    (net (code "40") (name "TDO") (class "Default")
      (node (ref "IC1") (pin "16") (pinfunction "PA6-SPI_MISO/ADC6/TIM3CH1_16") (pintype "bidirectional"))
      (node (ref "R6") (pin "P$1") (pinfunction "1_P$1") (pintype "passive"))
    )
    (net (code "41") (name "TMS") (class "Default")
      (node (ref "IC1") (pin "14") (pinfunction "PA4-SPI_NSS/ADC4/USART2CK_14") (pintype "bidirectional"))
      (node (ref "R11") (pin "P$1") (pinfunction "1_P$1") (pintype "passive"))
    )
    (net (code "42") (name "TMS_PROT") (class "Default")
      (node (ref "J1") (pin "2") (pinfunction "S_2") (pintype "passive"))
      (node (ref "J4") (pin "P$1") (pinfunction "1_P$1") (pintype "bidirectional"))
      (node (ref "R11") (pin "P$2") (pinfunction "2_P$2") (pintype "passive"))
    )
    (net (code "43") (name "TPWR") (class "Default")
      (node (ref "J1") (pin "1") (pinfunction "S_1") (pintype "passive"))
      (node (ref "J2") (pin "1") (pinfunction "1_1") (pintype "bidirectional"))
      (node (ref "J3") (pin "1") (pinfunction "1_1") (pintype "passive"))
      (node (ref "Q1") (pin "D") (pinfunction "D_D") (pintype "passive"))
      (node (ref "R8") (pin "P$2") (pinfunction "2_P$2") (pintype "passive"))
    )
    (net (code "44") (name "USBDM") (class "Default")
      (node (ref "IC1") (pin "32") (pinfunction "PA11-USART1CTS/USBDM_32") (pintype "bidirectional"))
      (node (ref "U20") (pin "3") (pinfunction "D2I_3") (pintype "bidirectional"))
    )
    (net (code "45") (name "USBDP") (class "Default")
      (node (ref "IC1") (pin "33") (pinfunction "PA12-USART1RTS/USBDP_33") (pintype "bidirectional"))
      (node (ref "U20") (pin "1") (pinfunction "D1I_1") (pintype "bidirectional"))
    )
    (net (code "46") (name "unconnected-(IC1-NRST-Pad7)") (class "Default")
      (node (ref "IC1") (pin "7") (pinfunction "NRST_7") (pintype "bidirectional"))
    )
    (net (code "47") (name "unconnected-(IC1-PA0-WKUP{slash}USART2CTS{slash}ADC0{slash}TIM2CH1ETR-Pad10)") (class "Default")
      (node (ref "IC1") (pin "10") (pinfunction "PA0-WKUP/USART2CTS/ADC0/TIM2CH1ETR_10") (pintype "bidirectional"))
    )
    (net (code "48") (name "unconnected-(IC1-PA1-USART2RTS{slash}ADC1{slash}TIM2CH2-Pad11)") (class "Default")
      (node (ref "IC1") (pin "11") (pinfunction "PA1-USART2RTS/ADC1/TIM2CH2_11") (pintype "bidirectional"))
    )
    (net (code "49") (name "unconnected-(IC1-PA7-SPI_MOSI{slash}ADC7{slash}TIM3CH2-Pad17)") (class "Default")
      (node (ref "IC1") (pin "17") (pinfunction "PA7-SPI_MOSI/ADC7/TIM3CH2_17") (pintype "bidirectional"))
    )
    (net (code "50") (name "unconnected-(IC1-PA15{slash}JTDI-TIM2CH1ETR{slash}SPI_NSS-Pad38)") (class "Default")
      (node (ref "IC1") (pin "38") (pinfunction "PA15/JTDI-TIM2CH1ETR/SPI_NSS_38") (pintype "bidirectional"))
    )
    (net (code "51") (name "unconnected-(IC1-PB3{slash}JTDO-TIM2CH2{slash}TRACESWO{slash}SPI_SCK-Pad39)") (class "Default")
      (node (ref "IC1") (pin "39") (pinfunction "PB3/JTDO-TIM2CH2/TRACESWO/SPI_SCK_39") (pintype "bidirectional"))
    )
    (net (code "52") (name "unconnected-(IC1-PB8-I2C_SCL-Pad45)") (class "Default")
      (node (ref "IC1") (pin "45") (pinfunction "PB8-I2C_SCL_45") (pintype "bidirectional"))
    )
    (net (code "53") (name "unconnected-(IC1-PB9-I2C_SDA-Pad46)") (class "Default")
      (node (ref "IC1") (pin "46") (pinfunction "PB9-I2C_SDA_46") (pintype "bidirectional"))
    )
    (net (code "54") (name "unconnected-(IC1-PB14-Pad27)") (class "Default")
      (node (ref "IC1") (pin "27") (pinfunction "PB14_27") (pintype "bidirectional"))
    )
    (net (code "55") (name "unconnected-(IC1-PB15-Pad28)") (class "Default")
      (node (ref "IC1") (pin "28") (pinfunction "PB15_28") (pintype "bidirectional"))
    )
    (net (code "56") (name "unconnected-(IC1-PC13-TAMPER-RTC-Pad2)") (class "Default")
      (node (ref "IC1") (pin "2") (pinfunction "PC13-TAMPER-RTC_2") (pintype "bidirectional"))
    )
    (net (code "57") (name "unconnected-(IC1-PC14-OSC32_IN-Pad3)") (class "Default")
      (node (ref "IC1") (pin "3") (pinfunction "PC14-OSC32_IN_3") (pintype "bidirectional"))
    )
    (net (code "58") (name "unconnected-(IC1-PC15-OSC32_OUT-Pad4)") (class "Default")
      (node (ref "IC1") (pin "4") (pinfunction "PC15-OSC32_OUT_4") (pintype "bidirectional"))
    )
    (net (code "59") (name "unconnected-(U$1-Pad2)") (class "Default")
      (node (ref "U$1") (pin "2") (pinfunction "2_2") (pintype "passive"))
    )
    (net (code "60") (name "unconnected-(U$1-Pad3)") (class "Default")
      (node (ref "U$1") (pin "3") (pinfunction "3_3") (pintype "passive"))
    )
  )
)
